# Power_N2V5.net
KiCad netlist of a schematic drawn in Altium Designer
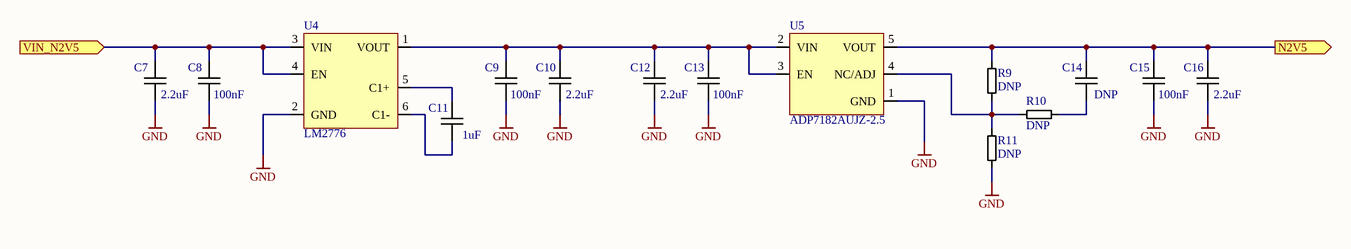
[diagram p0: Power_N2V5.SchDoc]

(export (version "E")
  (design (tool "Eeschema 10.0.6"))
  (components
    (comp (ref "C7")
      (value "2.2uF")
      (footprint "CAPC0603X90N")
      (description "Non-polarised capacitor")
      (fields (field (name "MANUFACTURER PART NUMBER") "GRM188Z71C225KE43D"))
      (libsource (lib "Capacitors") (part "Capacitor - non polarized"))
    )
    (comp (ref "C8")
      (value "100nF")
      (footprint "CAPC0603X90N")
      (description "Non-polarised capacitor")
      (fields (field (name "MANUFACTURER PART NUMBER") "VJ0603Y104KXJCW1BC"))
      (libsource (lib "Capacitors") (part "Capacitor - non polarized"))
    )
    (comp (ref "C9")
      (value "100nF")
      (footprint "CAPC0603X90N")
      (description "Non-polarised capacitor")
      (fields (field (name "MANUFACTURER PART NUMBER") "VJ0603Y104KXJCW1BC"))
      (libsource (lib "Capacitors") (part "Capacitor - non polarized"))
    )
    (comp (ref "C10")
      (value "2.2uF")
      (footprint "CAPC0603X90N")
      (description "Non-polarised capacitor")
      (fields (field (name "MANUFACTURER PART NUMBER") "GRM188Z71C225KE43D"))
      (libsource (lib "Capacitors") (part "Capacitor - non polarized"))
    )
    (comp (ref "C11")
      (value "1uF")
      (footprint "CAPC0603X90N")
      (description "Non-polarised capacitor")
      (fields (field (name "MANUFACTURER PART NUMBER") "CL10B105KO8NNNC"))
      (libsource (lib "Capacitors") (part "Capacitor - non polarized"))
    )
    (comp (ref "C12")
      (value "2.2uF")
      (footprint "CAPC0603X90N")
      (description "Non-polarised capacitor")
      (fields (field (name "MANUFACTURER PART NUMBER") "GRM188Z71C225KE43D"))
      (libsource (lib "Capacitors") (part "Capacitor - non polarized"))
    )
    (comp (ref "C13")
      (value "100nF")
      (footprint "CAPC0603X90N")
      (description "Non-polarised capacitor")
      (fields (field (name "MANUFACTURER PART NUMBER") "VJ0603Y104KXJCW1BC"))
      (libsource (lib "Capacitors") (part "Capacitor - non polarized"))
    )
    (comp (ref "C14")
      (value "DNP")
      (footprint "CAPC0603X90N")
      (description "Non-polarised capacitor")
      (fields (field (name "MANUFACTURER PART NUMBER") "UNDEFINED"))
      (libsource (lib "Capacitors") (part "Capacitor - non polarized"))
    )
    (comp (ref "C15")
      (value "100nF")
      (footprint "CAPC0603X90N")
      (description "Non-polarised capacitor")
      (fields (field (name "MANUFACTURER PART NUMBER") "VJ0603Y104KXJCW1BC"))
      (libsource (lib "Capacitors") (part "Capacitor - non polarized"))
    )
    (comp (ref "C16")
      (value "2.2uF")
      (footprint "CAPC0603X90N")
      (description "Non-polarised capacitor")
      (fields (field (name "MANUFACTURER PART NUMBER") "GRM188Z71C225KE43D"))
      (libsource (lib "Capacitors") (part "Capacitor - non polarized"))
    )
    (comp (ref "R9")
      (value "DNP")
      (footprint "RESC0402X40N")
      (description "General Purpose Thick Film Chip Resistor")
      (fields (field (name "VOLTAGE") "50V"))
      (libsource (lib "Resistors") (part "Resistor - Generic"))
    )
    (comp (ref "R10")
      (value "DNP")
      (footprint "RESC0402X40N")
      (description "General Purpose Thick Film Chip Resistor")
      (fields (field (name "VOLTAGE") "50V"))
      (libsource (lib "Resistors") (part "Resistor - Generic"))
    )
    (comp (ref "R11")
      (value "DNP")
      (footprint "RESC0402X40N")
      (description "General Purpose Thick Film Chip Resistor")
      (fields (field (name "VOLTAGE") "50V"))
      (libsource (lib "Resistors") (part "Resistor - Generic"))
    )
    (comp (ref "U4")
      (value "LM2776")
      (description "Switched Capacitor Inverter, Input Voltage: 2.7 V to 5.5 V, 200-mA Output Current")
      (fields (field (name "MANUFACTURER PART NUMBER") "LM2776DBV(_)"))
      (libsource (lib "ICs_and_Semiconductors") (part "LM2776"))
    )
    (comp (ref "U5")
      (value "ADP7182AUJZ-2.5")
      (description "LDO Voltage Regulators -30V, 200mA, low noise, Linear Reg, 2.5V")
      (libsource (lib "ICs_and_Semiconductors") (part "ADP7182AUJZ"))
    )
  )
  (nets
    (net (code "1") (name "/N2V5") (class "Default")
      (node (ref "C14") (pin "1") (pinfunction "1_1") (pintype "passive"))
      (node (ref "C15") (pin "1") (pinfunction "1_1") (pintype "passive"))
      (node (ref "C16") (pin "1") (pinfunction "1_1") (pintype "passive"))
      (node (ref "R9") (pin "2") (pinfunction "2_2") (pintype "passive"))
      (node (ref "U5") (pin "5") (pinfunction "VOUT_5") (pintype "power_in"))
    )
    (net (code "2") (name "/VIN_N2V5") (class "Default")
      (node (ref "C7") (pin "1") (pinfunction "1_1") (pintype "passive"))
      (node (ref "C8") (pin "1") (pinfunction "1_1") (pintype "passive"))
      (node (ref "U4") (pin "3") (pinfunction "VIN_3") (pintype "power_in"))
      (node (ref "U4") (pin "4") (pinfunction "EN_4") (pintype "passive"))
    )
    (net (code "3") (name "GND") (class "Default")
      (node (ref "C10") (pin "2") (pinfunction "2_2") (pintype "passive"))
      (node (ref "C12") (pin "2") (pinfunction "2_2") (pintype "passive"))
      (node (ref "C13") (pin "2") (pinfunction "2_2") (pintype "passive"))
      (node (ref "C15") (pin "2") (pinfunction "2_2") (pintype "passive"))
      (node (ref "C16") (pin "2") (pinfunction "2_2") (pintype "passive"))
      (node (ref "C7") (pin "2") (pinfunction "2_2") (pintype "passive"))
      (node (ref "C8") (pin "2") (pinfunction "2_2") (pintype "passive"))
      (node (ref "C9") (pin "2") (pinfunction "2_2") (pintype "passive"))
      (node (ref "R11") (pin "1") (pinfunction "1_1") (pintype "passive"))
      (node (ref "U4") (pin "2") (pinfunction "GND_2") (pintype "power_in"))
      (node (ref "U5") (pin "1") (pinfunction "GND_1") (pintype "power_in"))
    )
    (net (code "4") (name "Net-(C14-Pad2)") (class "Default")
      (node (ref "C14") (pin "2") (pinfunction "2_2") (pintype "passive"))
      (node (ref "R10") (pin "1") (pinfunction "1_1") (pintype "passive"))
    )
    (net (code "5") (name "Net-(U4-C1+)") (class "Default")
      (node (ref "C11") (pin "1") (pinfunction "1_1") (pintype "passive"))
      (node (ref "U4") (pin "5") (pinfunction "C1+_5") (pintype "passive"))
    )
    (net (code "6") (name "Net-(U4-C1-)") (class "Default")
      (node (ref "C11") (pin "2") (pinfunction "2_2") (pintype "passive"))
      (node (ref "U4") (pin "6") (pinfunction "C1-_6") (pintype "passive"))
    )
    (net (code "7") (name "Net-(U4-VOUT)") (class "Default")
      (node (ref "C10") (pin "1") (pinfunction "1_1") (pintype "passive"))
      (node (ref "C12") (pin "1") (pinfunction "1_1") (pintype "passive"))
      (node (ref "C13") (pin "1") (pinfunction "1_1") (pintype "passive"))
      (node (ref "C9") (pin "1") (pinfunction "1_1") (pintype "passive"))
      (node (ref "U4") (pin "1") (pinfunction "VOUT_1") (pintype "power_in"))
      (node (ref "U5") (pin "2") (pinfunction "VIN_2") (pintype "power_in"))
      (node (ref "U5") (pin "3") (pinfunction "EN_3") (pintype "passive"))
    )
    (net (code "8") (name "Net-(U5-NC{slash}ADJ)") (class "Default")
      (node (ref "R10") (pin "2") (pinfunction "2_2") (pintype "passive"))
      (node (ref "R11") (pin "2") (pinfunction "2_2") (pintype "passive"))
      (node (ref "R9") (pin "1") (pinfunction "1_1") (pintype "passive"))
      (node (ref "U5") (pin "4") (pinfunction "NC/ADJ_4") (pintype "passive"))
    )
  )
)
